# SCH_nfc_card_2024-09-17.net
KiCad netlist of a schematic drawn in EasyEDA
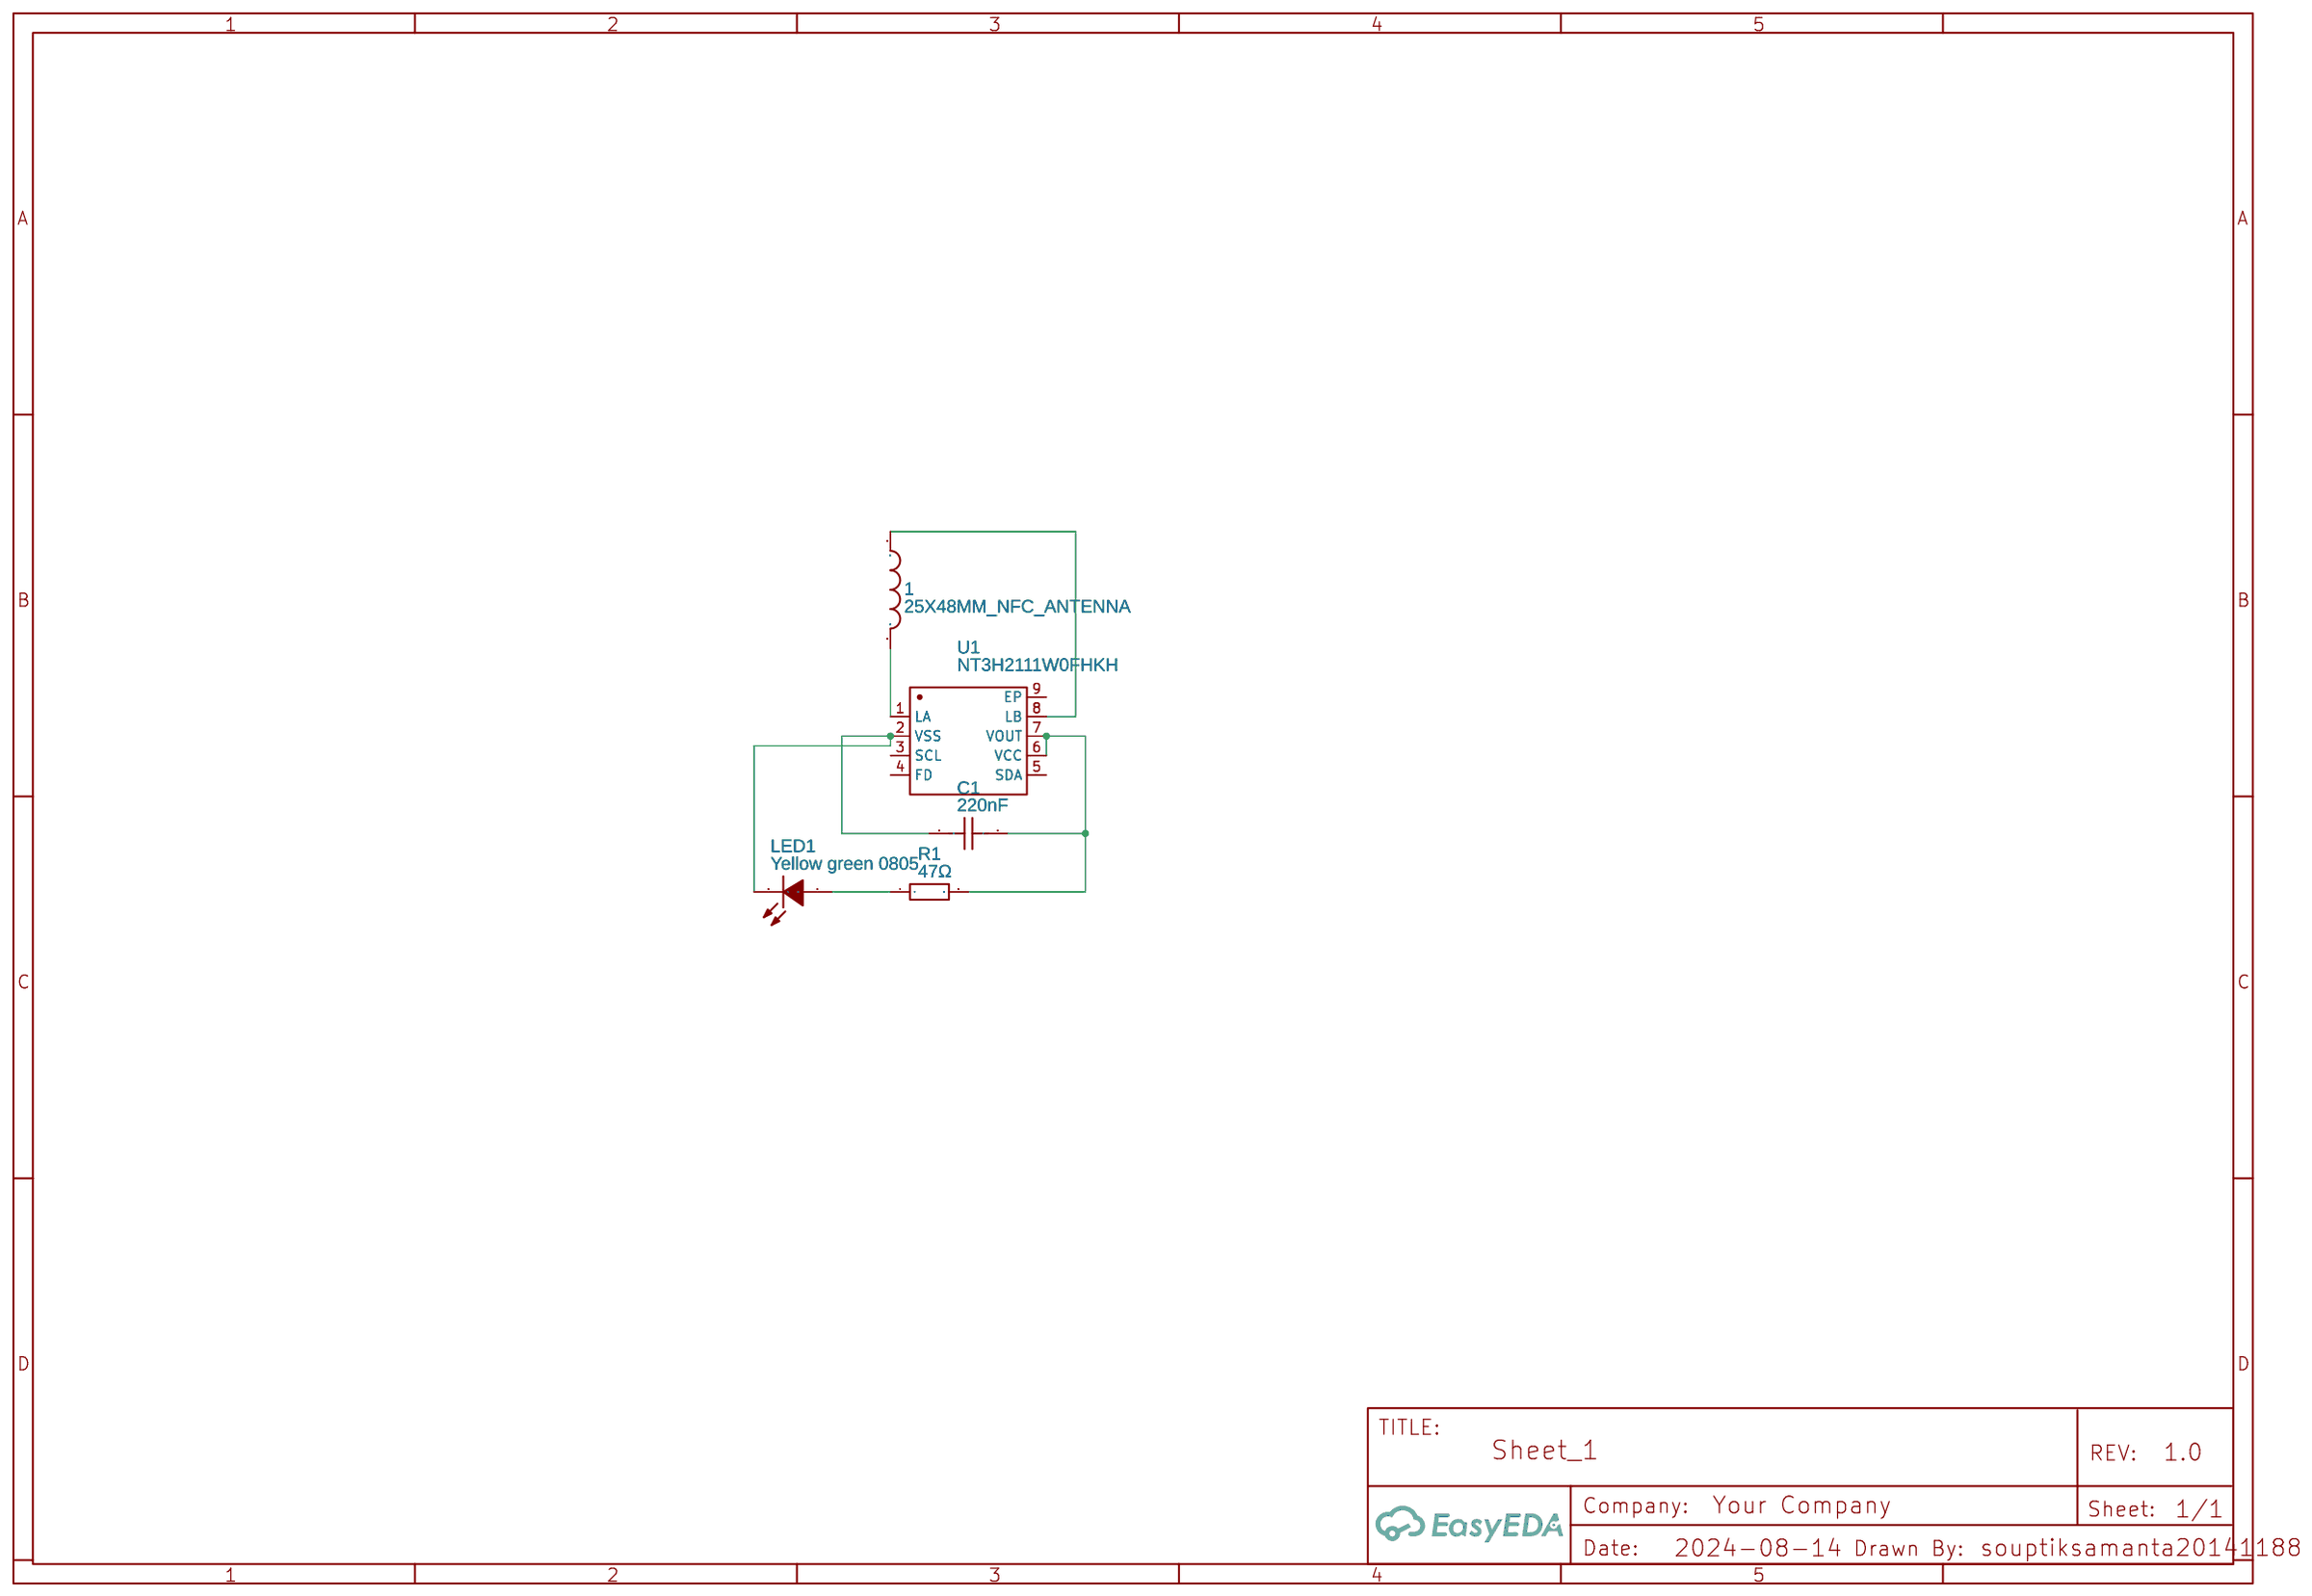
[diagram p0: schematic sheet]

(export (version "E")
  (design (tool "Eeschema 10.0.6"))
  (components
    (comp (ref "1") (value "25X48MM_NFC_ANTENNA") (libsource (lib "") (part "25X48MM_NFC_ANTENNA")))
    (comp (ref "C1")
      (value "220nF")
      (fields (field (name "Manufacturer Part") "0805B224K500NT") (field (name "Manufacturer") "FH(风华)"))
      (libsource (lib "") (part "0805B224K500NT"))
    )
    (comp (ref "LED1")
      (value "Yellow green 0805")
      (fields (field (name "Manufacturer Part") "KT-0805YG") (field (name "Manufacturer") "KENTO"))
      (libsource (lib "") (part "Yellow green 0805"))
    )
    (comp (ref "R1")
      (value "47Ω")
      (fields
        (field (name "Manufacturer Part") "0603WAF470JT5E")
        (field (name "Manufacturer") "UNI-ROYAL(厚声)")
      )
      (libsource (lib "") (part "0603WAF470JT5E"))
    )
    (comp (ref "U1")
      (value "NT3H2111W0FHKH")
      (fields (field (name "Manufacturer") "NXP(恩智浦)"))
      (libsource (lib "") (part "NT3H2111W0FHKH"))
    )
  )
  (nets
    (net (code "1") (name "Net-(LED1-A)") (class "Default")
      (node (ref "LED1") (pin "1") (pinfunction "A_1") (pintype "unspecified"))
      (node (ref "R1") (pin "1") (pinfunction "1_1") (pintype "input"))
    )
    (net (code "2") (name "Net-(LED1-K)") (class "Default")
      (node (ref "C1") (pin "2") (pinfunction "2_2") (pintype "unspecified"))
      (node (ref "LED1") (pin "2") (pinfunction "K_2") (pintype "unspecified"))
      (node (ref "U1") (pin "2") (pinfunction "VSS_2") (pintype "unspecified"))
    )
    (net (code "3") (name "Net-(U1-LA)") (class "Default")
      (node (ref "1") (pin "P$2") (pinfunction "P$2_P$2") (pintype "bidirectional"))
      (node (ref "U1") (pin "1") (pinfunction "LA_1") (pintype "unspecified"))
    )
    (net (code "4") (name "Net-(U1-LB)") (class "Default")
      (node (ref "1") (pin "P$1") (pinfunction "P$1_P$1") (pintype "bidirectional"))
      (node (ref "U1") (pin "8") (pinfunction "LB_8") (pintype "unspecified"))
    )
    (net (code "5") (name "Net-(U1-VCC)") (class "Default")
      (node (ref "C1") (pin "1") (pinfunction "1_1") (pintype "unspecified"))
      (node (ref "R1") (pin "2") (pinfunction "2_2") (pintype "input"))
      (node (ref "U1") (pin "6") (pinfunction "VCC_6") (pintype "unspecified"))
      (node (ref "U1") (pin "7") (pinfunction "VOUT_7") (pintype "unspecified"))
    )
    (net (code "6") (name "unconnected-(U1-EP-Pad9)") (class "Default")
      (node (ref "U1") (pin "9") (pinfunction "EP_9") (pintype "unspecified"))
    )
    (net (code "7") (name "unconnected-(U1-FD-Pad4)") (class "Default")
      (node (ref "U1") (pin "4") (pinfunction "FD_4") (pintype "unspecified"))
    )
    (net (code "8") (name "unconnected-(U1-SCL-Pad3)") (class "Default")
      (node (ref "U1") (pin "3") (pinfunction "SCL_3") (pintype "unspecified"))
    )
    (net (code "9") (name "unconnected-(U1-SDA-Pad5)") (class "Default")
      (node (ref "U1") (pin "5") (pinfunction "SDA_5") (pintype "unspecified"))
    )
  )
)
